# Sensor_Board.net
KiCad netlist of a schematic drawn in Altium Designer
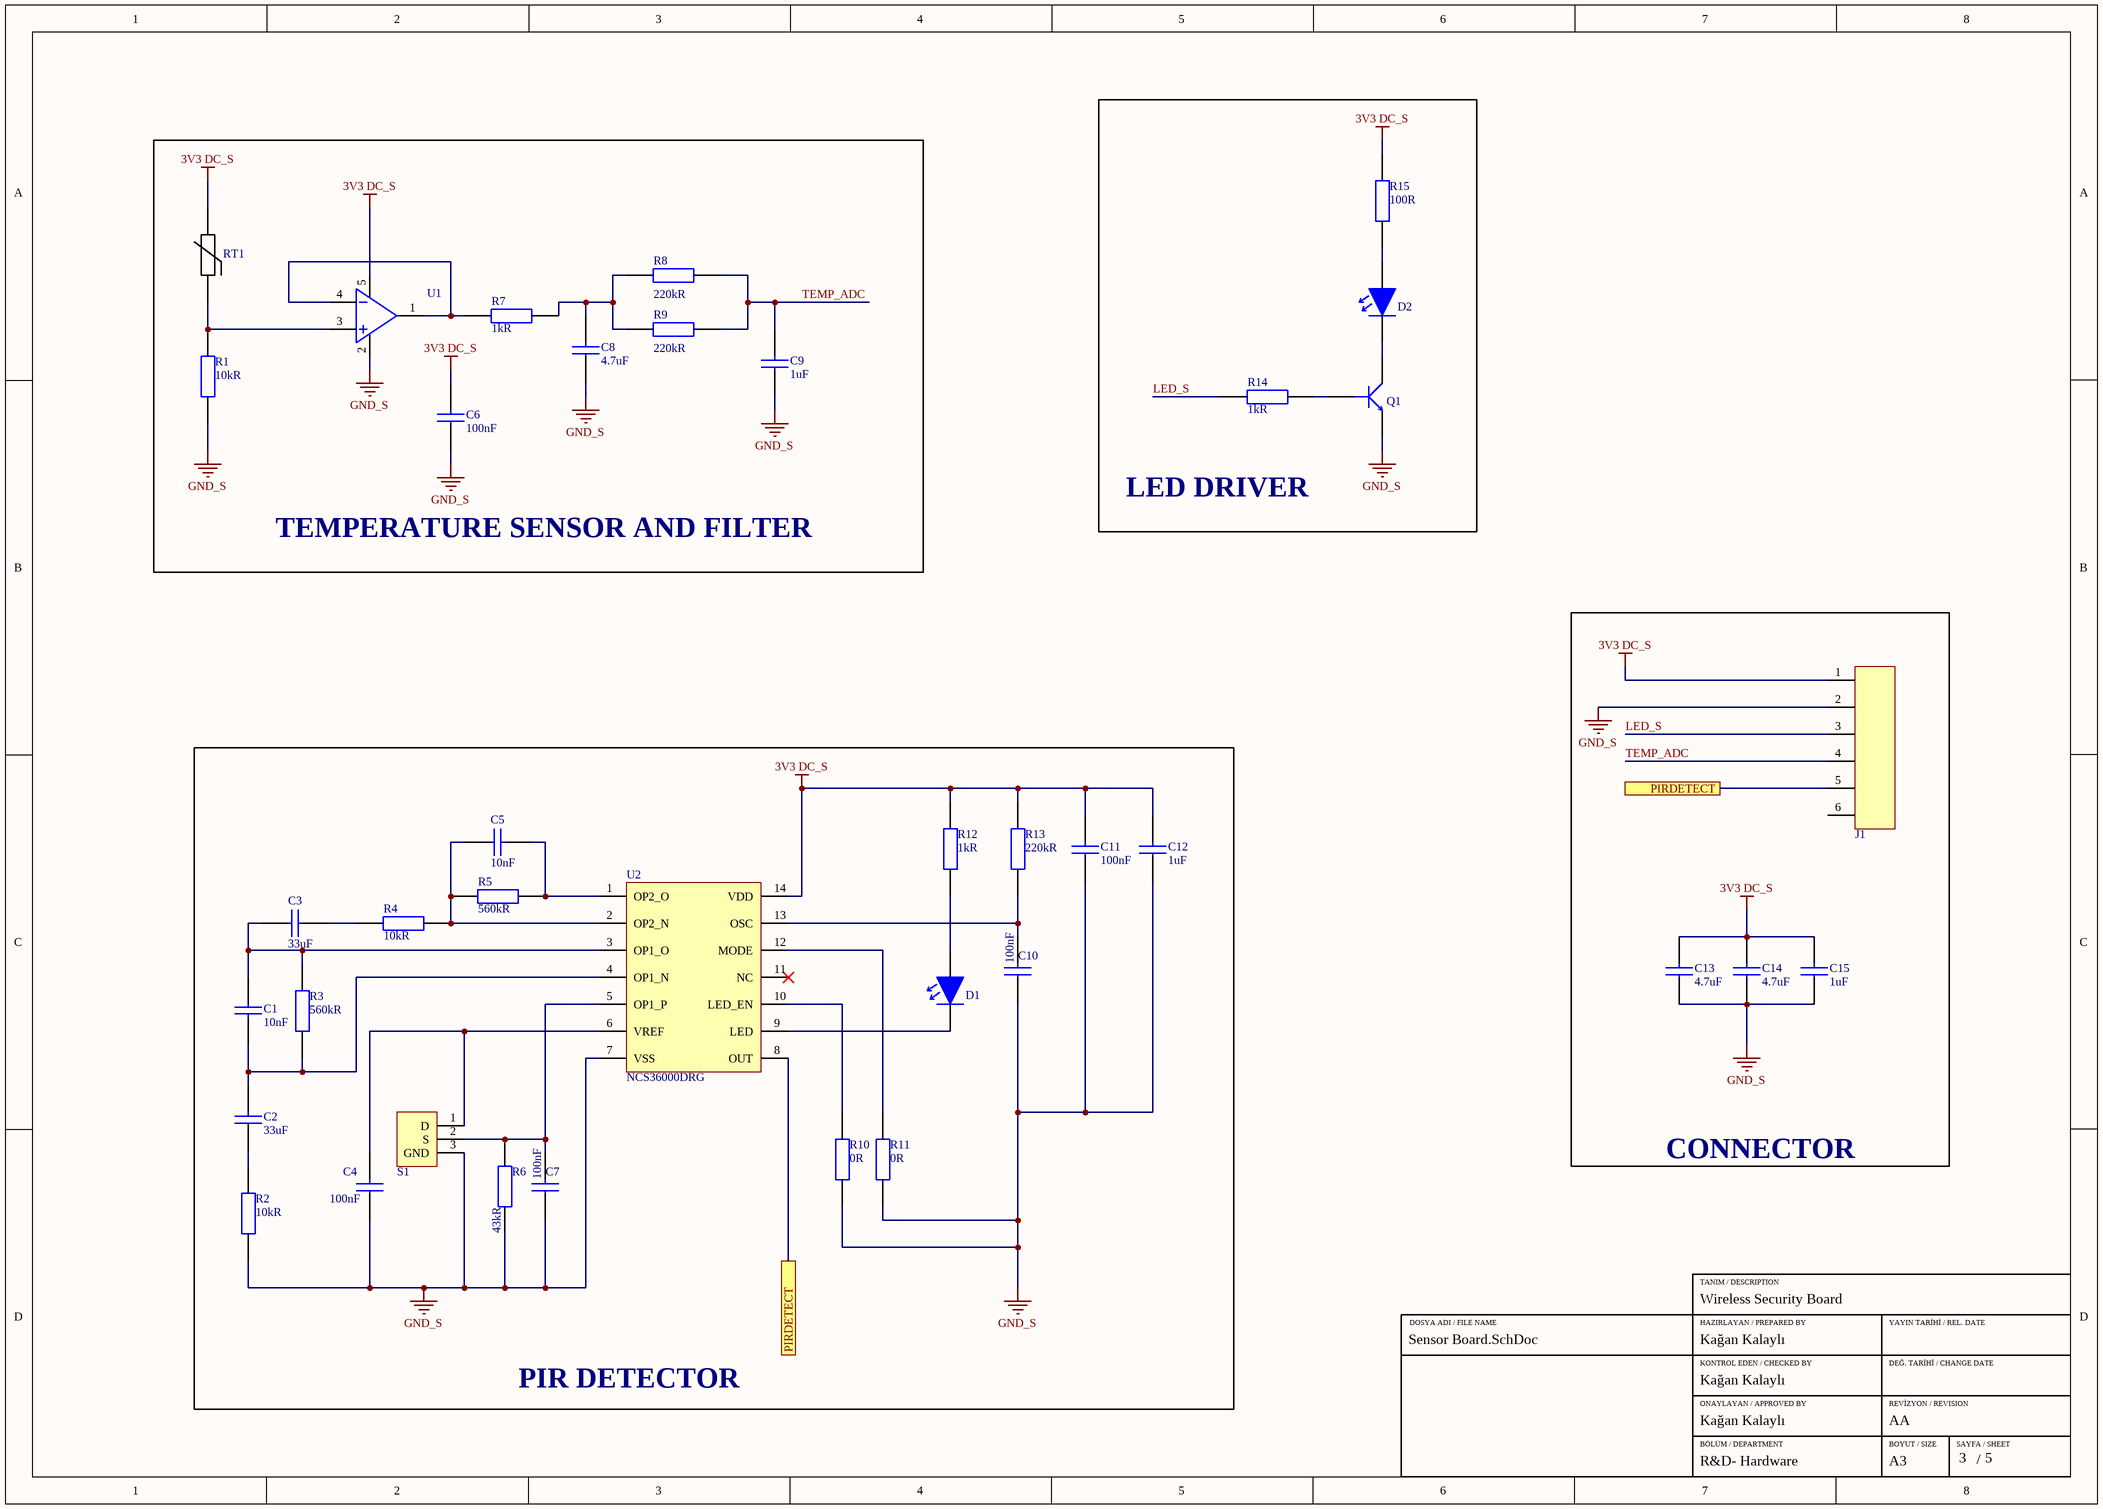
[diagram p0: Sensor Board.SchDoc]

(export (version "E")
  (design (tool "Eeschema 10.0.6"))
  (components
    (comp (ref "C1")
      (value "0603B103K160CT")
      (footprint "CAP_0603")
      (description "CAP CER 10nF %10 0603")
      (fields
        (field (name "MANUFACTURER") "Walsin Technologies")
        (field (name "TOLERANCE") "10%")
        (field (name "CAPACITANCE") "10nF")
        (field (name "DESIGNED BY") "Kağan")
      )
      (libsource (lib "Udemy_Library") (part "CAP CER 10nF 0603"))
    )
    (comp (ref "C2")
      (value "C3216X5R1E336M160AC")
      (footprint "CAP_1206")
      (description "CAP CER 33uF %20 1206 SMD")
      (fields
        (field (name "MANUFACTURER") "TDK")
        (field (name "TOLERANCE") "20%")
        (field (name "CAPACITANCE") "33uF")
        (field (name "DESIGNED BY") "Kağan")
      )
      (libsource (lib "Udemy_Library") (part "CAP CER 33uF 1206"))
    )
    (comp (ref "C3")
      (value "C3216X5R1E336M160AC")
      (footprint "CAP_1206")
      (description "CAP CER 33uF %20 1206 SMD")
      (fields
        (field (name "MANUFACTURER") "TDK")
        (field (name "TOLERANCE") "20%")
        (field (name "CAPACITANCE") "33uF")
        (field (name "DESIGNED BY") "Kağan")
      )
      (libsource (lib "Udemy_Library") (part "CAP CER 33uF 1206"))
    )
    (comp (ref "C4")
      (value "C0603C104K5RACTU")
      (footprint "CAP_0603")
      (description "CAP CER 100nF %10 0603 SMD")
      (fields
        (field (name "MANUFACTURER") "KEMET")
        (field (name "TOLERANCE") "10%")
        (field (name "CAPACITANCE") "100nF")
        (field (name "DESIGNED BY") "Kağan")
      )
      (libsource (lib "Udemy_Library") (part "CAP CER 100nF 0603_1"))
    )
    (comp (ref "C5")
      (value "0603B103K160CT")
      (footprint "CAP_0603")
      (description "CAP CER 10nF %10 0603")
      (fields
        (field (name "MANUFACTURER") "Walsin Technologies")
        (field (name "TOLERANCE") "10%")
        (field (name "CAPACITANCE") "10nF")
        (field (name "DESIGNED BY") "Kağan")
      )
      (libsource (lib "Udemy_Library") (part "CAP CER 10nF 0603"))
    )
    (comp (ref "C6")
      (value "C0603C104K5RACTU")
      (footprint "CAP_0603")
      (description "CAP CER 100nF %10 0603 SMD")
      (fields
        (field (name "MANUFACTURER") "KEMET")
        (field (name "TOLERANCE") "10%")
        (field (name "CAPACITANCE") "100nF")
        (field (name "DESIGNED BY") "Kağan")
      )
      (libsource (lib "Udemy_Library") (part "CAP CER 100nF 0603_1"))
    )
    (comp (ref "C7")
      (value "C0603C104K5RACTU")
      (footprint "CAP_0603")
      (description "CAP CER 100nF %10 0603 SMD")
      (fields
        (field (name "MANUFACTURER") "KEMET")
        (field (name "TOLERANCE") "10%")
        (field (name "CAPACITANCE") "100nF")
        (field (name "DESIGNED BY") "Kağan")
      )
      (libsource (lib "Udemy_Library") (part "CAP CER 100nF 0603_1"))
    )
    (comp (ref "C8")
      (value "CL21A475KAQNNNE")
      (footprint "CAP_0805")
      (description "CAP CER 4.7uF %10 0805")
      (fields
        (field (name "MANUFACTURER") "Samsung")
        (field (name "TOLERANCE") "10%")
        (field (name "CAPACITANCE") "4.7uF")
        (field (name "DESIGNED BY") "Kağan")
      )
      (libsource (lib "Udemy_Library") (part "CAP CER 4.7uF 0805"))
    )
    (comp (ref "C9")
      (value "CL21B105KBFNNNE")
      (footprint "CAP_0805")
      (description "CAP CER 1uF %10 0805")
      (fields
        (field (name "MANUFACTURER") "Samsung")
        (field (name "TOLERANCE") "10%")
        (field (name "CAPACITANCE") "1uF")
        (field (name "DESIGNED BY") "Kağan")
      )
      (libsource (lib "Udemy_Library") (part "CAP CER 1uF 0805"))
    )
    (comp (ref "C10")
      (value "C0603C104K5RACTU")
      (footprint "CAP_0603")
      (description "CAP CER 100nF %10 0603 SMD")
      (fields
        (field (name "MANUFACTURER") "KEMET")
        (field (name "TOLERANCE") "10%")
        (field (name "CAPACITANCE") "100nF")
        (field (name "DESIGNED BY") "Kağan")
      )
      (libsource (lib "Udemy_Library") (part "CAP CER 100nF 0603_1"))
    )
    (comp (ref "C11")
      (value "C0603C104K5RACTU")
      (footprint "CAP_0603")
      (description "CAP CER 100nF %10 0603 SMD")
      (fields
        (field (name "MANUFACTURER") "KEMET")
        (field (name "TOLERANCE") "10%")
        (field (name "CAPACITANCE") "100nF")
        (field (name "DESIGNED BY") "Kağan")
      )
      (libsource (lib "Udemy_Library") (part "CAP CER 100nF 0603_1"))
    )
    (comp (ref "C12")
      (value "CL21B105KBFNNNE")
      (footprint "CAP_0805")
      (description "CAP CER 1uF %10 0805")
      (fields
        (field (name "MANUFACTURER") "Samsung")
        (field (name "TOLERANCE") "10%")
        (field (name "CAPACITANCE") "1uF")
        (field (name "DESIGNED BY") "Kağan")
      )
      (libsource (lib "Udemy_Library") (part "CAP CER 1uF 0805"))
    )
    (comp (ref "C13")
      (value "CL21A475KAQNNNE")
      (footprint "CAP_0805")
      (description "CAP CER 4.7uF %10 0805")
      (fields
        (field (name "MANUFACTURER") "Samsung")
        (field (name "TOLERANCE") "10%")
        (field (name "CAPACITANCE") "4.7uF")
        (field (name "DESIGNED BY") "Kağan")
      )
      (libsource (lib "Udemy_Library") (part "CAP CER 4.7uF 0805"))
    )
    (comp (ref "C14")
      (value "CL21A475KAQNNNE")
      (footprint "CAP_0805")
      (description "CAP CER 4.7uF %10 0805")
      (fields
        (field (name "MANUFACTURER") "Samsung")
        (field (name "TOLERANCE") "10%")
        (field (name "CAPACITANCE") "4.7uF")
        (field (name "DESIGNED BY") "Kağan")
      )
      (libsource (lib "Udemy_Library") (part "CAP CER 4.7uF 0805"))
    )
    (comp (ref "C15")
      (value "CL21B105KBFNNNE")
      (footprint "CAP_0805")
      (description "CAP CER 1uF %10 0805")
      (fields
        (field (name "MANUFACTURER") "Samsung")
        (field (name "TOLERANCE") "10%")
        (field (name "CAPACITANCE") "1uF")
        (field (name "DESIGNED BY") "Kağan")
      )
      (libsource (lib "Udemy_Library") (part "CAP CER 1uF 0805"))
    )
    (comp (ref "D1")
      (value "LTST-C171GKT")
      (footprint "LED_GREEN_0805")
      (description "Green 0805 130 º Min 5 mcd Typical 12 mcd Water Clear Lens SMT LED")
      (fields (field (name "MANUFACTURER") "Vishay Lite-On") (field (name "DESIGNED BY") "Kağan"))
      (libsource (lib "Udemy_Library") (part "LED GREEN 0805"))
    )
    (comp (ref "D2")
      (value "LH R974-LP-1")
      (footprint "LED_RED_0805")
      (description "LED Uni-Color Hyper Red 660nm 2-Pin Chip 0805(2012Metric) T/R")
      (fields (field (name "MANUFACTURER") "Osram Opto") (field (name "DESIGNED BY") "Kağan"))
      (libsource (lib "Udemy_Library") (part "LED RED 0805"))
    )
    (comp (ref "J1")
      (value "64800611622")
      (footprint "64800611622")
      (description "1.50mm 6PIN Connector")
      (fields (field (name "MANUFACTURER") "Wurth Electronics") (field (name "DESIGNED BY") "Kağan"))
      (libsource (lib "Udemy_Library") (part "64800611622_conn_6pin"))
    )
    (comp (ref "Q1")
      (value "MMBT3904-7-F")
      (footprint "SOT-23F")
      (description "Transistor General Purpose BJT NPN 40 Volt 0.2A Automotive 3-Pin SOT-23")
      (fields (field (name "MANUFACTURER") "Diodes Zetex") (field (name "DESIGNED BY") "Kağan"))
      (libsource (lib "Udemy_Library") (part "MMBT3904-7-F"))
    )
    (comp (ref "R1")
      (value "RC0603FR-0710KL")
      (footprint "RES_0603")
      (description "RES 10K %1 OHM 0603 SMD")
      (fields
        (field (name "MANUFACTURER") "Yageo")
        (field (name "TOLERANCE") "1%")
        (field (name "RESISTANCE") "10kR")
        (field (name "DESIGNED BY") "Kağan")
      )
      (libsource (lib "Udemy_Library") (part "RES 10K OHM 0603"))
    )
    (comp (ref "R2")
      (value "RC0603FR-0710KL")
      (footprint "RES_0603")
      (description "RES 10K %1 OHM 0603 SMD")
      (fields
        (field (name "MANUFACTURER") "Yageo")
        (field (name "TOLERANCE") "1%")
        (field (name "RESISTANCE") "10kR")
        (field (name "DESIGNED BY") "Kağan")
      )
      (libsource (lib "Udemy_Library") (part "RES 10K OHM 0603"))
    )
    (comp (ref "R3")
      (value "RC0603JR-07560KL")
      (footprint "RES_0603")
      (description "RES SMD 560K OHM 5% 1/10W 0603")
      (fields
        (field (name "MANUFACTURER") "Yageo")
        (field (name "TOLERANCE") "5%")
        (field (name "RESISTANCE") "560kR")
        (field (name "DESIGNED BY") "Kağan")
      )
      (libsource (lib "") (part "RES 560K OHM 0603_1"))
    )
    (comp (ref "R4")
      (value "RC0603FR-0710KL")
      (footprint "RES_0603")
      (description "RES 10K %1 OHM 0603 SMD")
      (fields
        (field (name "MANUFACTURER") "Yageo")
        (field (name "TOLERANCE") "1%")
        (field (name "RESISTANCE") "10kR")
        (field (name "DESIGNED BY") "Kağan")
      )
      (libsource (lib "") (part "RES 10K OHM 0603_1"))
    )
    (comp (ref "R5")
      (value "RC0603JR-07560KL")
      (footprint "RES_0603")
      (description "RES SMD 560K OHM 5% 1/10W 0603")
      (fields
        (field (name "MANUFACTURER") "Yageo")
        (field (name "TOLERANCE") "5%")
        (field (name "RESISTANCE") "560kR")
        (field (name "DESIGNED BY") "Kağan")
      )
      (libsource (lib "Udemy_Library") (part "RES 560K OHM 0603"))
    )
    (comp (ref "R6")
      (value "RC0603JR-0743KL")
      (footprint "RES_0603")
      (description "RES 43K %5 OHM 0603 SMD")
      (fields
        (field (name "MANUFACTURER") "Yageo")
        (field (name "TOLERANCE") "5%")
        (field (name "RESISTANCE") "43kR")
        (field (name "DESIGNED BY") "Kağan")
      )
      (libsource (lib "Udemy_Library") (part "RES 43K OHM 0603"))
    )
    (comp (ref "R7")
      (value "RC0603FR-0710KL")
      (footprint "RES_0603")
      (description "RES 1K %1 OHM 0603 SMD")
      (fields
        (field (name "MANUFACTURER") "Yageo")
        (field (name "MANUFACTURER PART NUMBER") "RC0603JR-071KL")
        (field (name "RESISTANCE") "1kR")
        (field (name "DESIGNED BY") "Kağan")
      )
      (libsource (lib "Udemy_Library") (part "RES 1K OHM 0603"))
    )
    (comp (ref "R8")
      (value "RC0603JR-07220KL")
      (footprint "RES_0603")
      (description "RES 220K %5 OHM 0603 SMD")
      (fields
        (field (name "MANUFACTURER") "Yageo")
        (field (name "TOLERANCE") "5%")
        (field (name "RESISTANCE") "220kR")
      )
      (libsource (lib "Udemy_Library") (part "RES 220K OHM 0603"))
    )
    (comp (ref "R9")
      (value "RC0603JR-07220KL")
      (footprint "RES_0603")
      (description "RES 220K %5 OHM 0603 SMD")
      (fields
        (field (name "MANUFACTURER") "Yageo")
        (field (name "TOLERANCE") "5%")
        (field (name "RESISTANCE") "220kR")
      )
      (libsource (lib "Udemy_Library") (part "RES 220K OHM 0603"))
    )
    (comp (ref "R10")
      (value "RC0603JR-070RL")
      (footprint "RES_0603")
      (description "RES 0 %1 OHM 0603 SMD")
      (fields
        (field (name "MANUFACTURER") "Yageo")
        (field (name "TOLERANCE") "1%")
        (field (name "RESISTANCE") "0R")
        (field (name "DESIGNED BY") "Kağan")
      )
      (libsource (lib "Udemy_Library") (part "RES 0 OHM 0603"))
    )
    (comp (ref "R11")
      (value "RC0603JR-070RL")
      (footprint "RES_0603")
      (description "RES 0 %1 OHM 0603 SMD")
      (fields
        (field (name "MANUFACTURER") "Yageo")
        (field (name "TOLERANCE") "1%")
        (field (name "RESISTANCE") "0R")
        (field (name "DESIGNED BY") "Kağan")
      )
      (libsource (lib "Udemy_Library") (part "RES 0 OHM 0603"))
    )
    (comp (ref "R12")
      (value "RC0603FR-0710KL")
      (footprint "RES_0603")
      (description "RES 1K %1 OHM 0603 SMD")
      (fields
        (field (name "MANUFACTURER") "Yageo")
        (field (name "MANUFACTURER PART NUMBER") "RC0603JR-071KL")
        (field (name "RESISTANCE") "1kR")
        (field (name "DESIGNED BY") "Kağan")
      )
      (libsource (lib "") (part "RES 1K OHM 0603_1"))
    )
    (comp (ref "R13")
      (value "RC0603JR-07220KL")
      (footprint "RES_0603")
      (description "RES 220K %5 OHM 0603 SMD")
      (fields
        (field (name "MANUFACTURER") "Yageo")
        (field (name "TOLERANCE") "5%")
        (field (name "RESISTANCE") "220kR")
      )
      (libsource (lib "") (part "RES 220K OHM 0603_1"))
    )
    (comp (ref "R14")
      (value "RC0603FR-0710KL")
      (footprint "RES_0603")
      (description "RES 1K %1 OHM 0603 SMD")
      (fields
        (field (name "MANUFACTURER") "Yageo")
        (field (name "MANUFACTURER PART NUMBER") "RC0603JR-071KL")
        (field (name "RESISTANCE") "1kR")
        (field (name "DESIGNED BY") "Kağan")
      )
      (libsource (lib "Udemy_Library") (part "RES 1K OHM 0603"))
    )
    (comp (ref "R15")
      (value "RC0603JR-07100RL")
      (footprint "RES_0603")
      (description "RES 100 %5 OHM 0603 SMD")
      (fields
        (field (name "MANUFACTURER") "Yageo")
        (field (name "TOLERANCE") "5%")
        (field (name "RESISTANCE") "100R")
        (field (name "DESIGNED BY") "Kağan")
      )
      (libsource (lib "Udemy_Library") (part "RES 100 OHM 0603"))
    )
    (comp (ref "RT1")
      (value "TFPT1206L1002FM")
      (footprint "RES_1206")
      (description "Thermistor PTC 10K Ohm 1% 2-Pin 1206 Surface Mount Solder Pad T/R Automotive")
      (fields
        (field (name "MANUFACTURER") "Vishay Dale")
        (field (name "TOLERANCE") "1%")
        (field (name "DESIGNED BY") "Kağan")
      )
      (libsource (lib "Udemy_Library") (part "TFPT1206L1002FM"))
    )
    (comp (ref "S1")
      (value "LHI 878/3902")
      (footprint "LHI 878")
      (description "Sensor PIR (Passive Infrared) - - TO-205AA, TO-5-3 Metal Can")
      (fields
        (field (name "MANUFACTURER") "Excelitas")
        (field (name "MANUFACTURER PART NUMBER") "LHI878/3902")
        (field (name "DESIGNED BY") "Kağan")
      )
      (libsource (lib "Udemy_Library") (part "LHI 878/3902"))
    )
    (comp (ref "U1")
      (value "OPA314AIDBVR")
      (footprint "SOT23-5")
      (description "Op Amp OPA314")
      (fields (field (name "MANUFACTURER") "Texas Instruments") (field (name "DESIGNED BY") "Kağan"))
      (libsource (lib "Udemy_Library") (part "OPA314"))
    )
    (comp (ref "U2")
      (value "NCS36000DRG")
      (footprint "SOIC14")
      (description "PIR Controller Low Noise Amplifiers and LDO Regulator 14-Pin SOIC N T/R")
      (fields (field (name "MANUFACTURER") "ON Semiconductor") (field (name "DESIGNED BY") "Kağan"))
      (libsource (lib "Udemy_Library") (part "NCS36000"))
    )
  )
  (nets
    (net (code "1") (name "/LED_S") (class "Default")
      (node (ref "J1") (pin "3") (pintype "power_in"))
      (node (ref "R14") (pin "1") (pinfunction "1_1") (pintype "passive"))
    )
    (net (code "2") (name "/PIRDETECT") (class "Default")
      (node (ref "J1") (pin "5") (pintype "power_in"))
      (node (ref "U2") (pin "8") (pinfunction "OUT_8") (pintype "passive"))
    )
    (net (code "3") (name "/TEMP_ADC") (class "Default")
      (node (ref "C9") (pin "2") (pinfunction "2_2") (pintype "passive"))
      (node (ref "J1") (pin "4") (pintype "power_in"))
      (node (ref "R8") (pin "2") (pinfunction "2_2") (pintype "passive"))
      (node (ref "R9") (pin "2") (pinfunction "2_2") (pintype "passive"))
    )
    (net (code "4") (name "3V3 DC_S") (class "Default")
      (node (ref "C11") (pin "2") (pinfunction "2_2") (pintype "passive"))
      (node (ref "C12") (pin "2") (pinfunction "2_2") (pintype "passive"))
      (node (ref "C13") (pin "2") (pinfunction "2_2") (pintype "passive"))
      (node (ref "C14") (pin "2") (pinfunction "2_2") (pintype "passive"))
      (node (ref "C15") (pin "2") (pinfunction "2_2") (pintype "passive"))
      (node (ref "C6") (pin "2") (pinfunction "2_2") (pintype "passive"))
      (node (ref "J1") (pin "1") (pintype "power_in"))
      (node (ref "R12") (pin "2") (pinfunction "2_2") (pintype "passive"))
      (node (ref "R13") (pin "2") (pinfunction "2_2") (pintype "passive"))
      (node (ref "R15") (pin "2") (pinfunction "2_2") (pintype "passive"))
      (node (ref "RT1") (pin "2") (pinfunction "1_2") (pintype "passive"))
      (node (ref "U1") (pin "5") (pinfunction "5_5") (pintype "passive"))
      (node (ref "U2") (pin "14") (pinfunction "VDD_14") (pintype "passive"))
    )
    (net (code "5") (name "GND_S") (class "Default")
      (node (ref "C10") (pin "1") (pinfunction "1_1") (pintype "passive"))
      (node (ref "C11") (pin "1") (pinfunction "1_1") (pintype "passive"))
      (node (ref "C12") (pin "1") (pinfunction "1_1") (pintype "passive"))
      (node (ref "C13") (pin "1") (pinfunction "1_1") (pintype "passive"))
      (node (ref "C14") (pin "1") (pinfunction "1_1") (pintype "passive"))
      (node (ref "C15") (pin "1") (pinfunction "1_1") (pintype "passive"))
      (node (ref "C4") (pin "1") (pinfunction "1_1") (pintype "passive"))
      (node (ref "C6") (pin "1") (pinfunction "1_1") (pintype "passive"))
      (node (ref "C7") (pin "1") (pinfunction "1_1") (pintype "passive"))
      (node (ref "C8") (pin "1") (pinfunction "1_1") (pintype "passive"))
      (node (ref "C9") (pin "1") (pinfunction "1_1") (pintype "passive"))
      (node (ref "J1") (pin "2") (pintype "power_in"))
      (node (ref "Q1") (pin "2") (pinfunction "E_2") (pintype "power_in"))
      (node (ref "R1") (pin "1") (pinfunction "1_1") (pintype "passive"))
      (node (ref "R10") (pin "1") (pinfunction "1_1") (pintype "passive"))
      (node (ref "R11") (pin "1") (pinfunction "1_1") (pintype "passive"))
      (node (ref "R2") (pin "1") (pinfunction "1_1") (pintype "passive"))
      (node (ref "R6") (pin "1") (pinfunction "1_1") (pintype "passive"))
      (node (ref "S1") (pin "3") (pinfunction "GND_3") (pintype "passive"))
      (node (ref "U1") (pin "2") (pinfunction "2_2") (pintype "passive"))
      (node (ref "U2") (pin "7") (pinfunction "VSS_7") (pintype "passive"))
    )
    (net (code "6") (name "Net-(C2-Pad1)") (class "Default")
      (node (ref "C2") (pin "1") (pinfunction "1_1") (pintype "passive"))
      (node (ref "R2") (pin "2") (pinfunction "2_2") (pintype "passive"))
    )
    (net (code "7") (name "Net-(C3-Pad2)") (class "Default")
      (node (ref "C3") (pin "2") (pinfunction "2_2") (pintype "passive"))
      (node (ref "R4") (pin "1") (pinfunction "1_1") (pintype "passive"))
    )
    (net (code "8") (name "Net-(C8-Pad2)") (class "Default")
      (node (ref "C8") (pin "2") (pinfunction "2_2") (pintype "passive"))
      (node (ref "R7") (pin "2") (pinfunction "2_2") (pintype "passive"))
      (node (ref "R8") (pin "1") (pinfunction "1_1") (pintype "passive"))
      (node (ref "R9") (pin "1") (pinfunction "1_1") (pintype "passive"))
    )
    (net (code "9") (name "Net-(D1-Pad2)") (class "Default")
      (node (ref "D1") (pin "2") (pinfunction "2_2") (pintype "power_in"))
      (node (ref "R12") (pin "1") (pinfunction "1_1") (pintype "passive"))
    )
    (net (code "10") (name "Net-(D2-Pad2)") (class "Default")
      (node (ref "D2") (pin "2") (pinfunction "2_2") (pintype "power_in"))
      (node (ref "R15") (pin "1") (pinfunction "1_1") (pintype "passive"))
    )
    (net (code "11") (name "Net-(Q1-B)") (class "Default")
      (node (ref "Q1") (pin "1") (pinfunction "B_1") (pintype "power_in"))
      (node (ref "R14") (pin "2") (pinfunction "2_2") (pintype "passive"))
    )
    (net (code "12") (name "Net-(Q1-C)") (class "Default")
      (node (ref "D2") (pin "1") (pinfunction "1_1") (pintype "power_in"))
      (node (ref "Q1") (pin "3") (pinfunction "C_3") (pintype "power_in"))
    )
    (net (code "13") (name "Net-(R7-Pad1)") (class "Default")
      (node (ref "R7") (pin "1") (pinfunction "1_1") (pintype "passive"))
      (node (ref "U1") (pin "1") (pinfunction "1_1") (pintype "passive"))
      (node (ref "U1") (pin "4") (pinfunction "4_4") (pintype "passive"))
    )
    (net (code "14") (name "Net-(RT1-0)") (class "Default")
      (node (ref "R1") (pin "2") (pinfunction "2_2") (pintype "passive"))
      (node (ref "RT1") (pin "1") (pinfunction "0_1") (pintype "passive"))
      (node (ref "U1") (pin "3") (pinfunction "3_3") (pintype "passive"))
    )
    (net (code "15") (name "Net-(S1-D)") (class "Default")
      (node (ref "C4") (pin "2") (pinfunction "2_2") (pintype "passive"))
      (node (ref "S1") (pin "1") (pinfunction "D_1") (pintype "passive"))
      (node (ref "U2") (pin "6") (pinfunction "VREF_6") (pintype "passive"))
    )
    (net (code "16") (name "Net-(S1-S)") (class "Default")
      (node (ref "C7") (pin "2") (pinfunction "2_2") (pintype "passive"))
      (node (ref "R6") (pin "2") (pinfunction "2_2") (pintype "passive"))
      (node (ref "S1") (pin "2") (pinfunction "S_2") (pintype "passive"))
      (node (ref "U2") (pin "5") (pinfunction "OP1_P_5") (pintype "passive"))
    )
    (net (code "17") (name "Net-(U2-LED)") (class "Default")
      (node (ref "D1") (pin "1") (pinfunction "1_1") (pintype "power_in"))
      (node (ref "U2") (pin "9") (pinfunction "LED_9") (pintype "passive"))
    )
    (net (code "18") (name "Net-(U2-LED_EN)") (class "Default")
      (node (ref "R10") (pin "2") (pinfunction "2_2") (pintype "passive"))
      (node (ref "U2") (pin "10") (pinfunction "LED_EN_10") (pintype "passive"))
    )
    (net (code "19") (name "Net-(U2-MODE)") (class "Default")
      (node (ref "R11") (pin "2") (pinfunction "2_2") (pintype "passive"))
      (node (ref "U2") (pin "12") (pinfunction "MODE_12") (pintype "passive"))
    )
    (net (code "20") (name "Net-(U2-OP1_N)") (class "Default")
      (node (ref "C1") (pin "2") (pinfunction "2_2") (pintype "passive"))
      (node (ref "C2") (pin "2") (pinfunction "2_2") (pintype "passive"))
      (node (ref "R3") (pin "1") (pinfunction "1_1") (pintype "passive"))
      (node (ref "U2") (pin "4") (pinfunction "OP1_N_4") (pintype "passive"))
    )
    (net (code "21") (name "Net-(U2-OP1_O)") (class "Default")
      (node (ref "C1") (pin "1") (pinfunction "1_1") (pintype "passive"))
      (node (ref "C3") (pin "1") (pinfunction "1_1") (pintype "passive"))
      (node (ref "R3") (pin "2") (pinfunction "2_2") (pintype "passive"))
      (node (ref "U2") (pin "3") (pinfunction "OP1_O_3") (pintype "passive"))
    )
    (net (code "22") (name "Net-(U2-OP2_N)") (class "Default")
      (node (ref "C5") (pin "1") (pinfunction "1_1") (pintype "passive"))
      (node (ref "R4") (pin "2") (pinfunction "2_2") (pintype "passive"))
      (node (ref "R5") (pin "1") (pinfunction "1_1") (pintype "passive"))
      (node (ref "U2") (pin "2") (pinfunction "OP2_N_2") (pintype "passive"))
    )
    (net (code "23") (name "Net-(U2-OP2_O)") (class "Default")
      (node (ref "C5") (pin "2") (pinfunction "2_2") (pintype "passive"))
      (node (ref "R5") (pin "2") (pinfunction "2_2") (pintype "passive"))
      (node (ref "U2") (pin "1") (pinfunction "OP2_O_1") (pintype "passive"))
    )
    (net (code "24") (name "Net-(U2-OSC)") (class "Default")
      (node (ref "C10") (pin "2") (pinfunction "2_2") (pintype "passive"))
      (node (ref "R13") (pin "1") (pinfunction "1_1") (pintype "passive"))
      (node (ref "U2") (pin "13") (pinfunction "OSC_13") (pintype "passive"))
    )
    (net (code "25") (name "unconnected-(J1-Pad6)") (class "Default")
      (node (ref "J1") (pin "6") (pintype "power_in"))
    )
    (net (code "26") (name "unconnected-(U2-NC-Pad11)") (class "Default")
      (node (ref "U2") (pin "11") (pinfunction "NC_11") (pintype "passive+no_connect"))
    )
  )
)
